# Apex_CV_Expander_MAIN_1_0.net
KiCad netlist of a schematic drawn in EAGLE
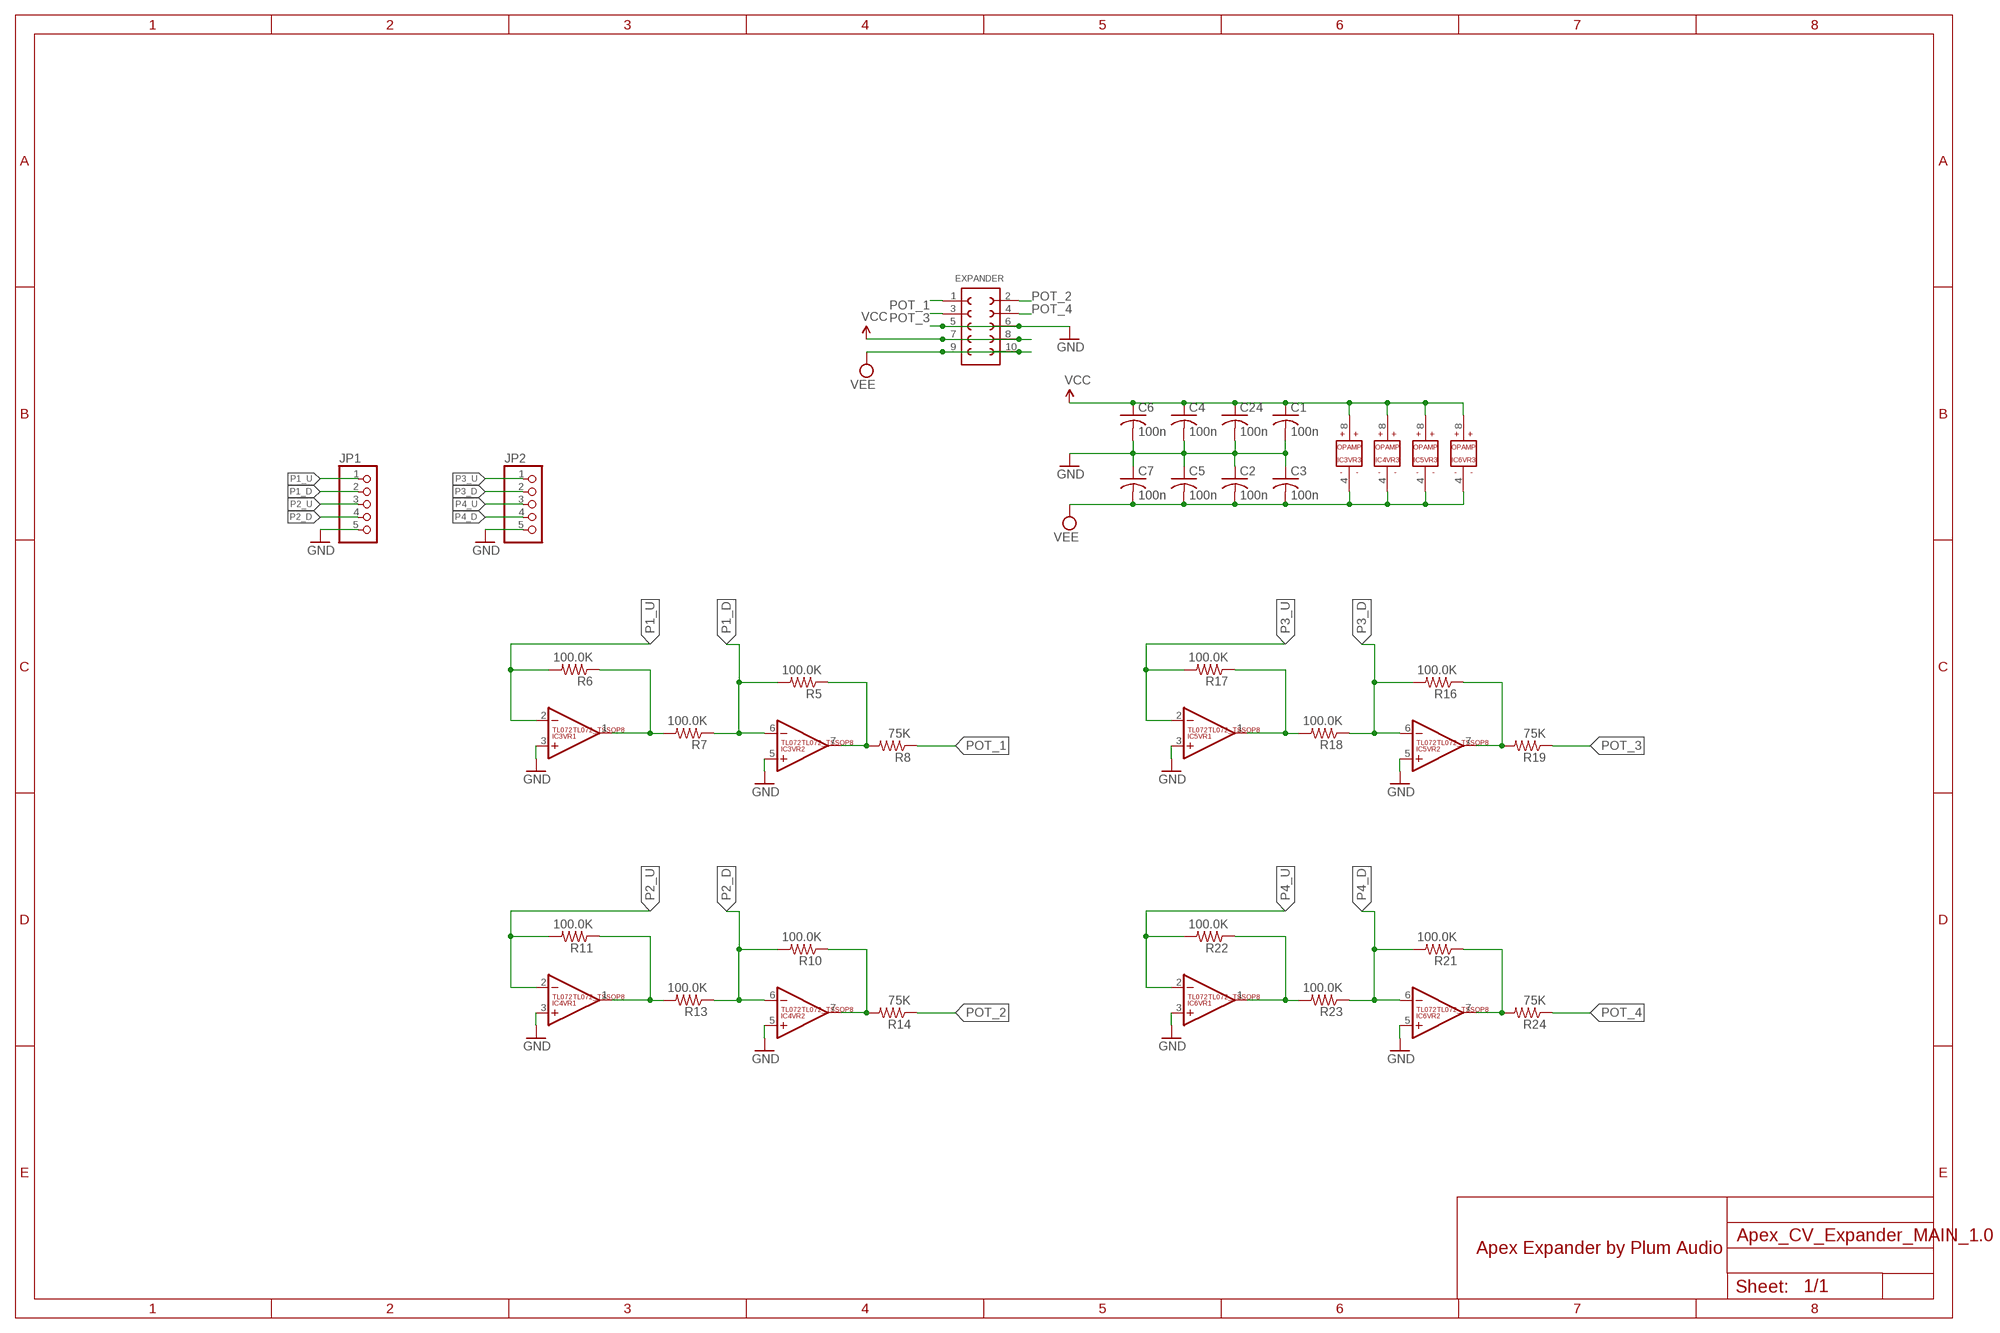
[diagram p0: schematic, sheet 1]

(export (version "E")
  (design (tool "Eeschema 10.0.6"))
  (components
    (comp (ref "C1")
      (value "100n")
      (footprint "eagle-import:C0603")
      (libsource (lib "eagle-import") (part "C-USC0603"))
    )
    (comp (ref "C2")
      (value "100n")
      (footprint "eagle-import:C0603")
      (libsource (lib "eagle-import") (part "C-USC0603"))
    )
    (comp (ref "C3")
      (value "100n")
      (footprint "eagle-import:C0603")
      (libsource (lib "eagle-import") (part "C-USC0603"))
    )
    (comp (ref "C4")
      (value "100n")
      (footprint "eagle-import:C0603")
      (libsource (lib "eagle-import") (part "C-USC0603"))
    )
    (comp (ref "C5")
      (value "100n")
      (footprint "eagle-import:C0603")
      (libsource (lib "eagle-import") (part "C-USC0603"))
    )
    (comp (ref "C6")
      (value "100n")
      (footprint "eagle-import:C0603")
      (libsource (lib "eagle-import") (part "C-USC0603"))
    )
    (comp (ref "C7")
      (value "100n")
      (footprint "eagle-import:C0603")
      (libsource (lib "eagle-import") (part "C-USC0603"))
    )
    (comp (ref "C24")
      (value "100n")
      (footprint "eagle-import:C0603")
      (libsource (lib "eagle-import") (part "C-USC0603"))
    )
    (comp (ref "EXPANDER")
      (value "61301021121")
      (footprint "eagle-import:61301021121")
      (libsource (lib "eagle-import") (part "61301021121"))
    )
    (comp (ref "IC3")
      (value "TL072TL072_TSSOP8")
      (footprint "eagle-import:TL072_TSSOP8")
      (libsource (lib "eagle-import") (part "TL072TL072_TSSOP8"))
    )
    (comp (ref "IC4")
      (value "TL072TL072_TSSOP8")
      (footprint "eagle-import:TL072_TSSOP8")
      (libsource (lib "eagle-import") (part "TL072TL072_TSSOP8"))
    )
    (comp (ref "IC5")
      (value "TL072TL072_TSSOP8")
      (footprint "eagle-import:TL072_TSSOP8")
      (libsource (lib "eagle-import") (part "TL072TL072_TSSOP8"))
    )
    (comp (ref "IC6")
      (value "TL072TL072_TSSOP8")
      (footprint "eagle-import:TL072_TSSOP8")
      (libsource (lib "eagle-import") (part "TL072TL072_TSSOP8"))
    )
    (comp (ref "JP1")
      (value "PINHD-1X5")
      (footprint "eagle-import:1X05")
      (libsource (lib "eagle-import") (part "PINHD-1X5"))
    )
    (comp (ref "JP2")
      (value "PINHD-1X5")
      (footprint "eagle-import:1X05")
      (libsource (lib "eagle-import") (part "PINHD-1X5"))
    )
    (comp (ref "R5")
      (value "100.0K")
      (footprint "eagle-import:R0603")
      (libsource (lib "eagle-import") (part "R-US_R0603"))
    )
    (comp (ref "R6")
      (value "100.0K")
      (footprint "eagle-import:R0603")
      (libsource (lib "eagle-import") (part "R-US_R0603"))
    )
    (comp (ref "R7")
      (value "100.0K")
      (footprint "eagle-import:R0603")
      (libsource (lib "eagle-import") (part "R-US_R0603"))
    )
    (comp (ref "R8")
      (value "75K")
      (footprint "eagle-import:R0603")
      (libsource (lib "eagle-import") (part "R-US_R0603"))
    )
    (comp (ref "R10")
      (value "100.0K")
      (footprint "eagle-import:R0603")
      (libsource (lib "eagle-import") (part "R-US_R0603"))
    )
    (comp (ref "R11")
      (value "100.0K")
      (footprint "eagle-import:R0603")
      (libsource (lib "eagle-import") (part "R-US_R0603"))
    )
    (comp (ref "R13")
      (value "100.0K")
      (footprint "eagle-import:R0603")
      (libsource (lib "eagle-import") (part "R-US_R0603"))
    )
    (comp (ref "R14")
      (value "75K")
      (footprint "eagle-import:R0603")
      (libsource (lib "eagle-import") (part "R-US_R0603"))
    )
    (comp (ref "R16")
      (value "100.0K")
      (footprint "eagle-import:R0603")
      (libsource (lib "eagle-import") (part "R-US_R0603"))
    )
    (comp (ref "R17")
      (value "100.0K")
      (footprint "eagle-import:R0603")
      (libsource (lib "eagle-import") (part "R-US_R0603"))
    )
    (comp (ref "R18")
      (value "100.0K")
      (footprint "eagle-import:R0603")
      (libsource (lib "eagle-import") (part "R-US_R0603"))
    )
    (comp (ref "R19")
      (value "75K")
      (footprint "eagle-import:R0603")
      (libsource (lib "eagle-import") (part "R-US_R0603"))
    )
    (comp (ref "R21")
      (value "100.0K")
      (footprint "eagle-import:R0603")
      (libsource (lib "eagle-import") (part "R-US_R0603"))
    )
    (comp (ref "R22")
      (value "100.0K")
      (footprint "eagle-import:R0603")
      (libsource (lib "eagle-import") (part "R-US_R0603"))
    )
    (comp (ref "R23")
      (value "100.0K")
      (footprint "eagle-import:R0603")
      (libsource (lib "eagle-import") (part "R-US_R0603"))
    )
    (comp (ref "R24")
      (value "75K")
      (footprint "eagle-import:R0603")
      (libsource (lib "eagle-import") (part "R-US_R0603"))
    )
  )
  (nets
    (net (code "1") (name "GND") (class "Default")
      (node (ref "C1") (pin "2") (pinfunction "2_2") (pintype "passive"))
      (node (ref "C2") (pin "1") (pinfunction "1_1") (pintype "passive"))
      (node (ref "C24") (pin "2") (pinfunction "2_2") (pintype "passive"))
      (node (ref "C3") (pin "1") (pinfunction "1_1") (pintype "passive"))
      (node (ref "C4") (pin "2") (pinfunction "2_2") (pintype "passive"))
      (node (ref "C5") (pin "1") (pinfunction "1_1") (pintype "passive"))
      (node (ref "C6") (pin "2") (pinfunction "2_2") (pintype "passive"))
      (node (ref "C7") (pin "1") (pinfunction "1_1") (pintype "passive"))
      (node (ref "EXPANDER") (pin "5") (pinfunction "3_5") (pintype "passive"))
      (node (ref "EXPANDER") (pin "6") (pinfunction "8_6") (pintype "passive"))
      (node (ref "IC3") (pin "3") (pinfunction "+IN_3") (pintype "input"))
      (node (ref "IC3") (pin "5") (pinfunction "+IN_5") (pintype "input"))
      (node (ref "IC4") (pin "3") (pinfunction "+IN_3") (pintype "input"))
      (node (ref "IC4") (pin "5") (pinfunction "+IN_5") (pintype "input"))
      (node (ref "IC5") (pin "3") (pinfunction "+IN_3") (pintype "input"))
      (node (ref "IC5") (pin "5") (pinfunction "+IN_5") (pintype "input"))
      (node (ref "IC6") (pin "3") (pinfunction "+IN_3") (pintype "input"))
      (node (ref "IC6") (pin "5") (pinfunction "+IN_5") (pintype "input"))
      (node (ref "JP1") (pin "5") (pinfunction "5_5") (pintype "passive"))
      (node (ref "JP2") (pin "5") (pinfunction "5_5") (pintype "passive"))
    )
    (net (code "2") (name "Net-(IC3A-OUT)") (class "Default")
      (node (ref "IC3") (pin "1") (pinfunction "OUT_1") (pintype "output"))
      (node (ref "R6") (pin "1") (pinfunction "1_1") (pintype "passive"))
      (node (ref "R7") (pin "2") (pinfunction "2_2") (pintype "passive"))
    )
    (net (code "3") (name "Net-(IC3B-OUT)") (class "Default")
      (node (ref "IC3") (pin "7") (pinfunction "OUT_7") (pintype "output"))
      (node (ref "R5") (pin "1") (pinfunction "1_1") (pintype "passive"))
      (node (ref "R8") (pin "2") (pinfunction "2_2") (pintype "passive"))
    )
    (net (code "4") (name "Net-(IC4A-OUT)") (class "Default")
      (node (ref "IC4") (pin "1") (pinfunction "OUT_1") (pintype "output"))
      (node (ref "R11") (pin "1") (pinfunction "1_1") (pintype "passive"))
      (node (ref "R13") (pin "2") (pinfunction "2_2") (pintype "passive"))
    )
    (net (code "5") (name "Net-(IC4B-OUT)") (class "Default")
      (node (ref "IC4") (pin "7") (pinfunction "OUT_7") (pintype "output"))
      (node (ref "R10") (pin "1") (pinfunction "1_1") (pintype "passive"))
      (node (ref "R14") (pin "2") (pinfunction "2_2") (pintype "passive"))
    )
    (net (code "6") (name "Net-(IC5A-OUT)") (class "Default")
      (node (ref "IC5") (pin "1") (pinfunction "OUT_1") (pintype "output"))
      (node (ref "R17") (pin "1") (pinfunction "1_1") (pintype "passive"))
      (node (ref "R18") (pin "2") (pinfunction "2_2") (pintype "passive"))
    )
    (net (code "7") (name "Net-(IC5B-OUT)") (class "Default")
      (node (ref "IC5") (pin "7") (pinfunction "OUT_7") (pintype "output"))
      (node (ref "R16") (pin "1") (pinfunction "1_1") (pintype "passive"))
      (node (ref "R19") (pin "2") (pinfunction "2_2") (pintype "passive"))
    )
    (net (code "8") (name "Net-(IC6A-OUT)") (class "Default")
      (node (ref "IC6") (pin "1") (pinfunction "OUT_1") (pintype "output"))
      (node (ref "R22") (pin "1") (pinfunction "1_1") (pintype "passive"))
      (node (ref "R23") (pin "2") (pinfunction "2_2") (pintype "passive"))
    )
    (net (code "9") (name "Net-(IC6B-OUT)") (class "Default")
      (node (ref "IC6") (pin "7") (pinfunction "OUT_7") (pintype "output"))
      (node (ref "R21") (pin "1") (pinfunction "1_1") (pintype "passive"))
      (node (ref "R24") (pin "2") (pinfunction "2_2") (pintype "passive"))
    )
    (net (code "10") (name "P1_D") (class "Default")
      (node (ref "IC3") (pin "6") (pinfunction "-IN_6") (pintype "input"))
      (node (ref "JP1") (pin "2") (pinfunction "2_2") (pintype "passive"))
      (node (ref "R5") (pin "2") (pinfunction "2_2") (pintype "passive"))
      (node (ref "R7") (pin "1") (pinfunction "1_1") (pintype "passive"))
    )
    (net (code "11") (name "P1_U") (class "Default")
      (node (ref "IC3") (pin "2") (pinfunction "-IN_2") (pintype "input"))
      (node (ref "JP1") (pin "1") (pinfunction "1_1") (pintype "passive"))
      (node (ref "R6") (pin "2") (pinfunction "2_2") (pintype "passive"))
    )
    (net (code "12") (name "P2_D") (class "Default")
      (node (ref "IC4") (pin "6") (pinfunction "-IN_6") (pintype "input"))
      (node (ref "JP1") (pin "4") (pinfunction "4_4") (pintype "passive"))
      (node (ref "R10") (pin "2") (pinfunction "2_2") (pintype "passive"))
      (node (ref "R13") (pin "1") (pinfunction "1_1") (pintype "passive"))
    )
    (net (code "13") (name "P2_U") (class "Default")
      (node (ref "IC4") (pin "2") (pinfunction "-IN_2") (pintype "input"))
      (node (ref "JP1") (pin "3") (pinfunction "3_3") (pintype "passive"))
      (node (ref "R11") (pin "2") (pinfunction "2_2") (pintype "passive"))
    )
    (net (code "14") (name "P3_D") (class "Default")
      (node (ref "IC5") (pin "6") (pinfunction "-IN_6") (pintype "input"))
      (node (ref "JP2") (pin "2") (pinfunction "2_2") (pintype "passive"))
      (node (ref "R16") (pin "2") (pinfunction "2_2") (pintype "passive"))
      (node (ref "R18") (pin "1") (pinfunction "1_1") (pintype "passive"))
    )
    (net (code "15") (name "P3_U") (class "Default")
      (node (ref "IC5") (pin "2") (pinfunction "-IN_2") (pintype "input"))
      (node (ref "JP2") (pin "1") (pinfunction "1_1") (pintype "passive"))
      (node (ref "R17") (pin "2") (pinfunction "2_2") (pintype "passive"))
    )
    (net (code "16") (name "P4_D") (class "Default")
      (node (ref "IC6") (pin "6") (pinfunction "-IN_6") (pintype "input"))
      (node (ref "JP2") (pin "4") (pinfunction "4_4") (pintype "passive"))
      (node (ref "R21") (pin "2") (pinfunction "2_2") (pintype "passive"))
      (node (ref "R23") (pin "1") (pinfunction "1_1") (pintype "passive"))
    )
    (net (code "17") (name "P4_U") (class "Default")
      (node (ref "IC6") (pin "2") (pinfunction "-IN_2") (pintype "input"))
      (node (ref "JP2") (pin "3") (pinfunction "3_3") (pintype "passive"))
      (node (ref "R22") (pin "2") (pinfunction "2_2") (pintype "passive"))
    )
    (net (code "18") (name "POT_1") (class "Default")
      (node (ref "EXPANDER") (pin "1") (pinfunction "1_1") (pintype "passive"))
      (node (ref "R8") (pin "1") (pinfunction "1_1") (pintype "passive"))
    )
    (net (code "19") (name "POT_2") (class "Default")
      (node (ref "EXPANDER") (pin "2") (pinfunction "10_2") (pintype "passive"))
      (node (ref "R14") (pin "1") (pinfunction "1_1") (pintype "passive"))
    )
    (net (code "20") (name "POT_3") (class "Default")
      (node (ref "EXPANDER") (pin "3") (pinfunction "2_3") (pintype "passive"))
      (node (ref "R19") (pin "1") (pinfunction "1_1") (pintype "passive"))
    )
    (net (code "21") (name "POT_4") (class "Default")
      (node (ref "EXPANDER") (pin "4") (pinfunction "9_4") (pintype "passive"))
      (node (ref "R24") (pin "1") (pinfunction "1_1") (pintype "passive"))
    )
    (net (code "22") (name "VCC") (class "Default")
      (node (ref "C1") (pin "1") (pinfunction "1_1") (pintype "passive"))
      (node (ref "C24") (pin "1") (pinfunction "1_1") (pintype "passive"))
      (node (ref "C4") (pin "1") (pinfunction "1_1") (pintype "passive"))
      (node (ref "C6") (pin "1") (pinfunction "1_1") (pintype "passive"))
      (node (ref "EXPANDER") (pin "7") (pinfunction "4_7") (pintype "passive"))
      (node (ref "EXPANDER") (pin "8") (pinfunction "7_8") (pintype "passive"))
      (node (ref "IC3") (pin "8") (pinfunction "V+_8") (pintype "power_in"))
      (node (ref "IC4") (pin "8") (pinfunction "V+_8") (pintype "power_in"))
      (node (ref "IC5") (pin "8") (pinfunction "V+_8") (pintype "power_in"))
      (node (ref "IC6") (pin "8") (pinfunction "V+_8") (pintype "power_in"))
    )
    (net (code "23") (name "VEE") (class "Default")
      (node (ref "C2") (pin "2") (pinfunction "2_2") (pintype "passive"))
      (node (ref "C3") (pin "2") (pinfunction "2_2") (pintype "passive"))
      (node (ref "C5") (pin "2") (pinfunction "2_2") (pintype "passive"))
      (node (ref "C7") (pin "2") (pinfunction "2_2") (pintype "passive"))
      (node (ref "EXPANDER") (pin "10") (pinfunction "6_10") (pintype "passive"))
      (node (ref "EXPANDER") (pin "9") (pinfunction "5_9") (pintype "passive"))
      (node (ref "IC3") (pin "4") (pinfunction "V-_4") (pintype "power_in"))
      (node (ref "IC4") (pin "4") (pinfunction "V-_4") (pintype "power_in"))
      (node (ref "IC5") (pin "4") (pinfunction "V-_4") (pintype "power_in"))
      (node (ref "IC6") (pin "4") (pinfunction "V-_4") (pintype "power_in"))
    )
  )
)
